# Buck_Regulator_secondary.net
KiCad netlist of a schematic drawn in EAGLE
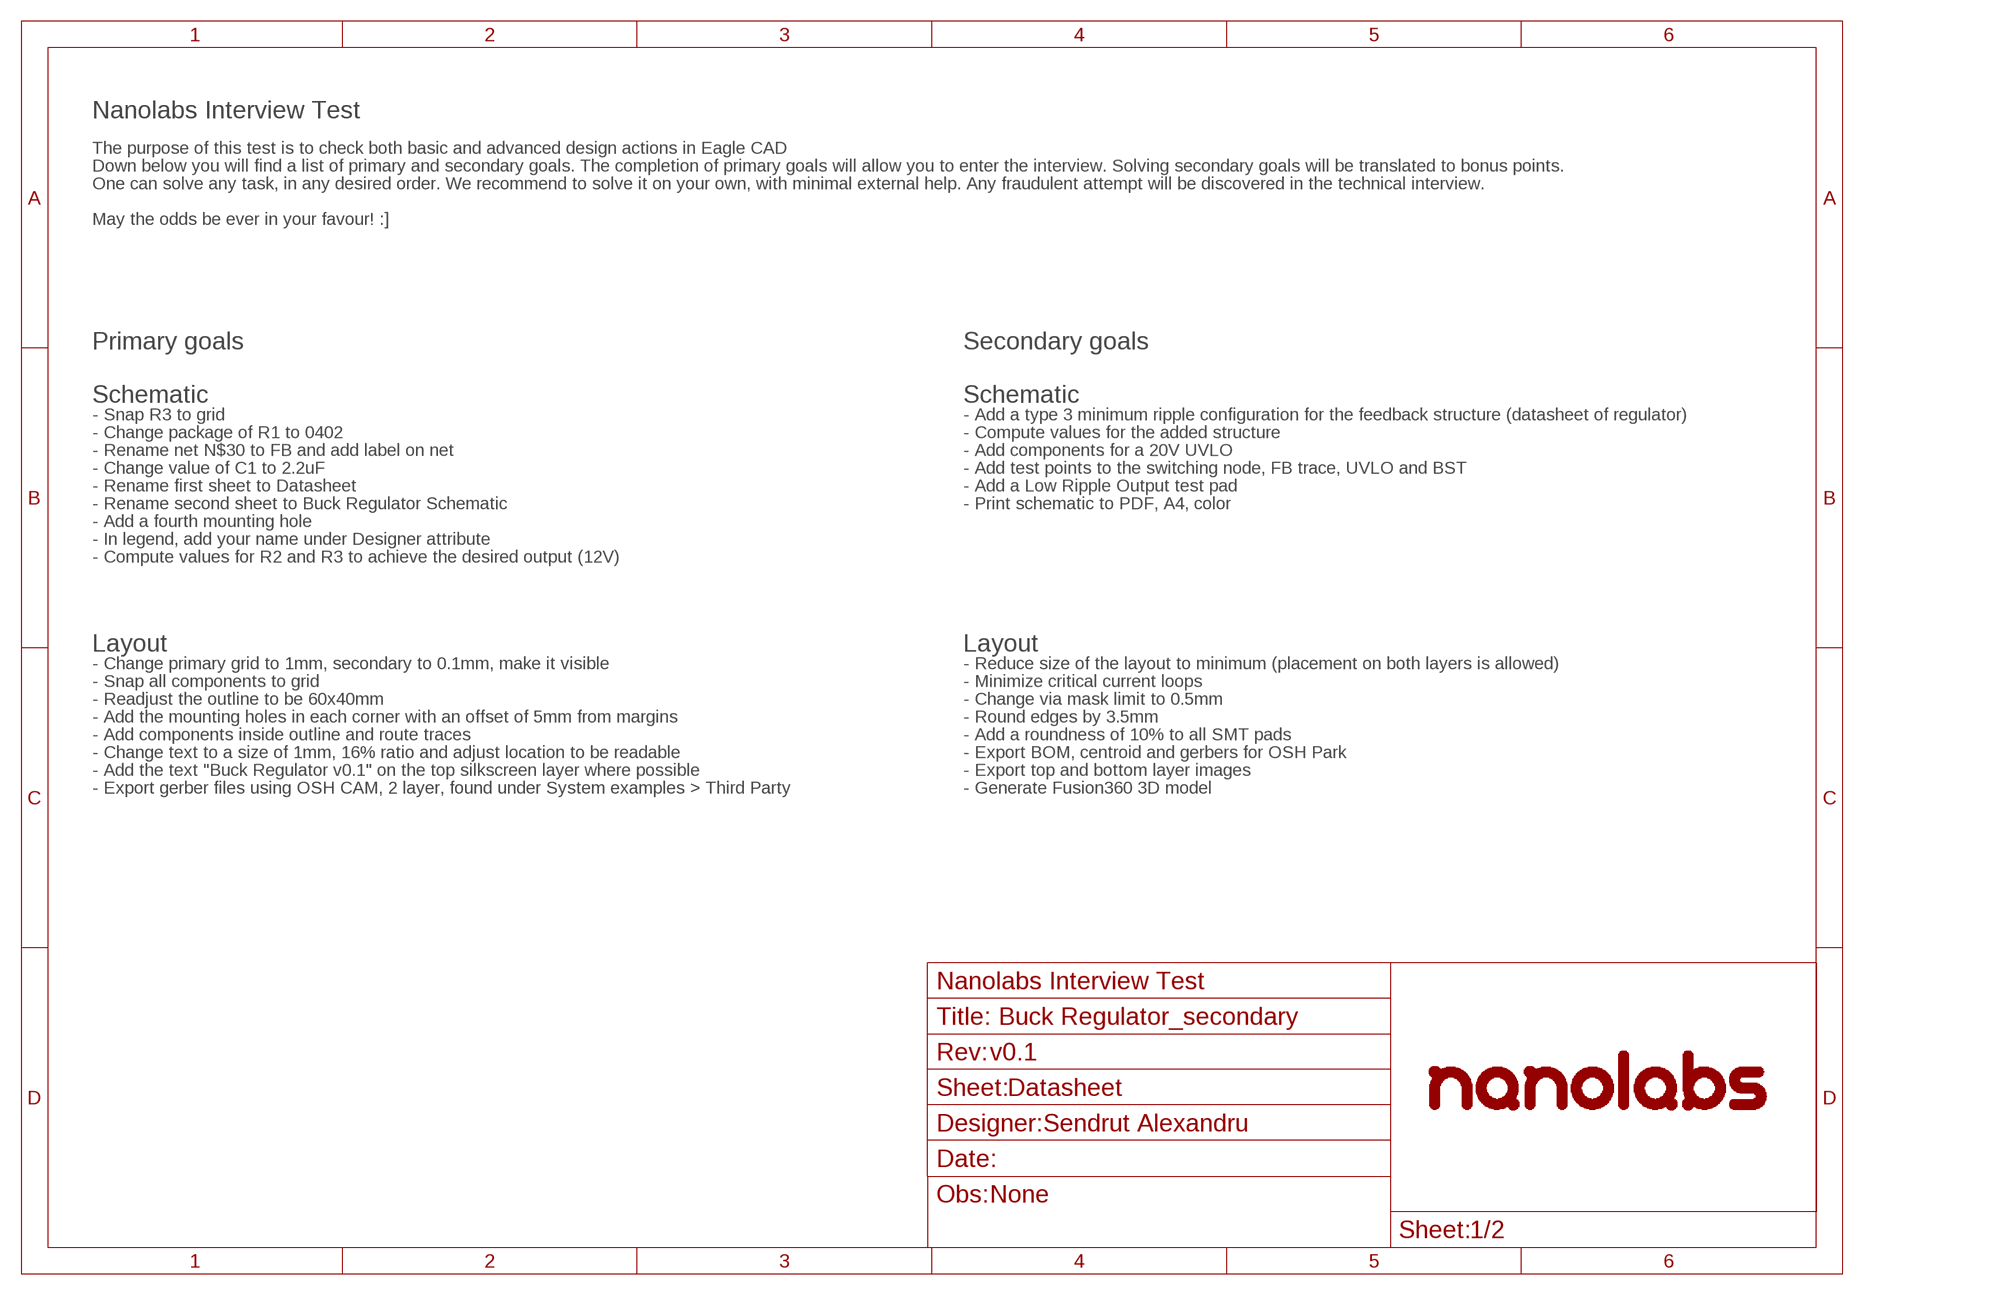
[diagram p0: schematic, sheet 1]
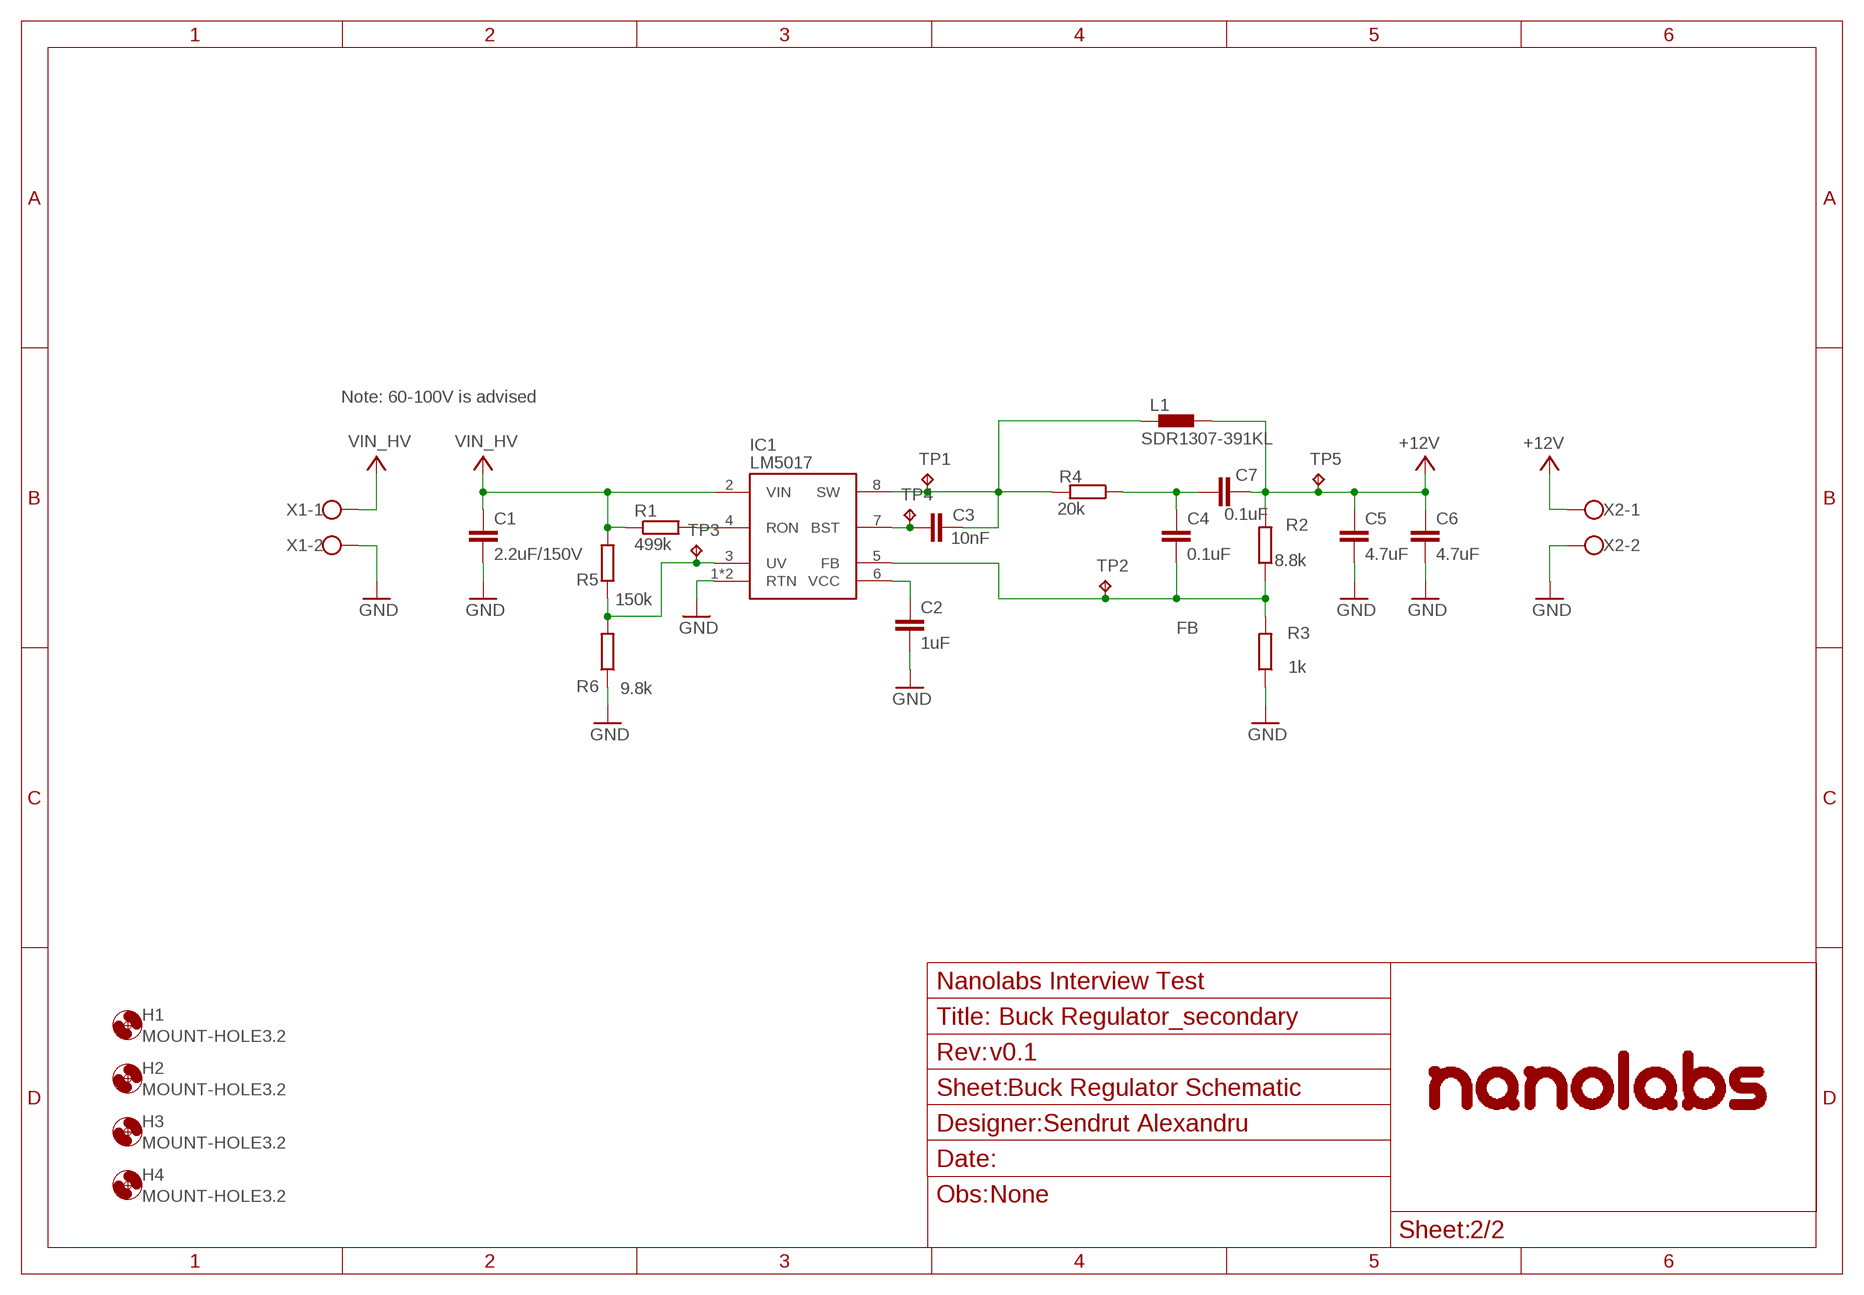
[diagram p1: schematic, sheet 2]

(export (version "E")
  (design (tool "Eeschema 10.0.6"))
  (components
    (comp (ref "C1")
      (value "2.2uF/150V")
      (footprint "eagle-import:C1812")
      (libsource (lib "eagle-import") (part "C-EUC1812"))
    )
    (comp (ref "C2")
      (value "1uF")
      (footprint "eagle-import:C0603")
      (libsource (lib "eagle-import") (part "C-EUC0603"))
    )
    (comp (ref "C3")
      (value "10nF")
      (footprint "eagle-import:C0603")
      (libsource (lib "eagle-import") (part "C-EUC0603"))
    )
    (comp (ref "C4")
      (value "0.1uF")
      (footprint "eagle-import:C0603")
      (libsource (lib "eagle-import") (part "C-EUC0603"))
    )
    (comp (ref "C5")
      (value "4.7uF")
      (footprint "eagle-import:C0603")
      (libsource (lib "eagle-import") (part "C-EUC0603"))
    )
    (comp (ref "C6")
      (value "4.7uF")
      (footprint "eagle-import:C0603")
      (libsource (lib "eagle-import") (part "C-EUC0603"))
    )
    (comp (ref "C7")
      (value "0.1uF")
      (footprint "eagle-import:C0603")
      (libsource (lib "eagle-import") (part "C-EUC0603"))
    )
    (comp (ref "H1")
      (value "MOUNT-HOLE3.2")
      (footprint "eagle-import:3,2")
      (libsource (lib "eagle-import") (part "MOUNT-HOLE3.2"))
    )
    (comp (ref "H2")
      (value "MOUNT-HOLE3.2")
      (footprint "eagle-import:3,2")
      (libsource (lib "eagle-import") (part "MOUNT-HOLE3.2"))
    )
    (comp (ref "H3")
      (value "MOUNT-HOLE3.2")
      (footprint "eagle-import:3,2")
      (libsource (lib "eagle-import") (part "MOUNT-HOLE3.2"))
    )
    (comp (ref "H4")
      (value "MOUNT-HOLE3.2")
      (footprint "eagle-import:3,2")
      (libsource (lib "eagle-import") (part "MOUNT-HOLE3.2"))
    )
    (comp (ref "IC1")
      (value "LM5017")
      (footprint "eagle-import:SO-08-EP")
      (libsource (lib "eagle-import") (part "LM5017"))
    )
    (comp (ref "L1")
      (value "SDR1307-391KL")
      (footprint "eagle-import:SDR1307-391KL")
      (libsource (lib "eagle-import") (part "SDR1307-391KL"))
    )
    (comp (ref "R1")
      (value "499k")
      (footprint "eagle-import:R0402")
      (libsource (lib "eagle-import") (part "R-EU_R0402"))
    )
    (comp (ref "R2")
      (value "8.8k")
      (footprint "eagle-import:R0603")
      (libsource (lib "eagle-import") (part "R-EU_R0603"))
    )
    (comp (ref "R3")
      (value "1k")
      (footprint "eagle-import:R0603")
      (libsource (lib "eagle-import") (part "R-EU_R0603"))
    )
    (comp (ref "R4")
      (value "20k")
      (footprint "eagle-import:R0603")
      (libsource (lib "eagle-import") (part "R-EU_R0603"))
    )
    (comp (ref "R5")
      (value "150k")
      (footprint "eagle-import:R0402")
      (libsource (lib "eagle-import") (part "R-EU_R0402"))
    )
    (comp (ref "R6")
      (value "9.8k")
      (footprint "eagle-import:R0402")
      (libsource (lib "eagle-import") (part "R-EU_R0402"))
    )
    (comp (ref "TP1")
      (value "TPB1,27")
      (footprint "eagle-import:B1,27")
      (libsource (lib "eagle-import") (part "TPB1,27"))
    )
    (comp (ref "TP2")
      (value "TPB1,27")
      (footprint "eagle-import:B1,27")
      (libsource (lib "eagle-import") (part "TPB1,27"))
    )
    (comp (ref "TP3")
      (value "TPB1,27")
      (footprint "eagle-import:B1,27")
      (libsource (lib "eagle-import") (part "TPB1,27"))
    )
    (comp (ref "TP4")
      (value "TPB1,27")
      (footprint "eagle-import:B1,27")
      (libsource (lib "eagle-import") (part "TPB1,27"))
    )
    (comp (ref "TP5")
      (value "TPB1,27")
      (footprint "eagle-import:B1,27")
      (libsource (lib "eagle-import") (part "TPB1,27"))
    )
    (comp (ref "X1")
      (value "W237-102")
      (footprint "eagle-import:W237-102")
      (fields (field (name "MPN") "237-102"))
      (libsource (lib "eagle-import") (part "W237-102"))
    )
    (comp (ref "X2")
      (value "W237-102")
      (footprint "eagle-import:W237-102")
      (fields (field (name "MPN") "237-102"))
      (libsource (lib "eagle-import") (part "W237-102"))
    )
  )
  (nets
    (net (code "1") (name "+12V") (class "Default")
      (node (ref "C5") (pin "1") (pinfunction "1_1") (pintype "passive"))
      (node (ref "C6") (pin "1") (pinfunction "1_1") (pintype "passive"))
      (node (ref "C7") (pin "2") (pinfunction "2_2") (pintype "passive"))
      (node (ref "L1") (pin "2") (pinfunction "2_2") (pintype "passive"))
      (node (ref "R2") (pin "2") (pinfunction "2_2") (pintype "passive"))
      (node (ref "TP5") (pin "TP") (pinfunction "TP_TP") (pintype "input"))
      (node (ref "X2") (pin "1") (pinfunction "KL_1") (pintype "passive"))
    )
    (net (code "2") (name "FB") (class "Default")
      (node (ref "C4") (pin "2") (pinfunction "2_2") (pintype "passive"))
      (node (ref "IC1") (pin "5") (pinfunction "FB_5") (pintype "bidirectional"))
      (node (ref "R2") (pin "1") (pinfunction "1_1") (pintype "passive"))
      (node (ref "R3") (pin "2") (pinfunction "2_2") (pintype "passive"))
      (node (ref "TP2") (pin "TP") (pinfunction "TP_TP") (pintype "input"))
    )
    (net (code "3") (name "GND") (class "Default")
      (node (ref "C1") (pin "2") (pinfunction "2_2") (pintype "passive"))
      (node (ref "C2") (pin "2") (pinfunction "2_2") (pintype "passive"))
      (node (ref "C5") (pin "2") (pinfunction "2_2") (pintype "passive"))
      (node (ref "C6") (pin "2") (pinfunction "2_2") (pintype "passive"))
      (node (ref "IC1") (pin "1") (pinfunction "RTN_1") (pintype "bidirectional"))
      (node (ref "IC1") (pin "9") (pinfunction "RTN_9") (pintype "bidirectional"))
      (node (ref "R3") (pin "1") (pinfunction "1_1") (pintype "passive"))
      (node (ref "R6") (pin "1") (pinfunction "1_1") (pintype "passive"))
      (node (ref "X1") (pin "2") (pinfunction "KL_2") (pintype "passive"))
      (node (ref "X2") (pin "2") (pinfunction "KL_2") (pintype "passive"))
    )
    (net (code "4") (name "Net-(C4-Pad1)") (class "Default")
      (node (ref "C4") (pin "1") (pinfunction "1_1") (pintype "passive"))
      (node (ref "C7") (pin "1") (pinfunction "1_1") (pintype "passive"))
      (node (ref "R4") (pin "1") (pinfunction "1_1") (pintype "passive"))
    )
    (net (code "5") (name "Net-(IC1-BST)") (class "Default")
      (node (ref "C3") (pin "1") (pinfunction "1_1") (pintype "passive"))
      (node (ref "IC1") (pin "7") (pinfunction "BST_7") (pintype "bidirectional"))
      (node (ref "TP4") (pin "TP") (pinfunction "TP_TP") (pintype "input"))
    )
    (net (code "6") (name "Net-(IC1-RON)") (class "Default")
      (node (ref "IC1") (pin "4") (pinfunction "RON_4") (pintype "bidirectional"))
      (node (ref "R1") (pin "2") (pinfunction "2_2") (pintype "passive"))
    )
    (net (code "7") (name "Net-(IC1-SW)") (class "Default")
      (node (ref "C3") (pin "2") (pinfunction "2_2") (pintype "passive"))
      (node (ref "IC1") (pin "8") (pinfunction "SW_8") (pintype "bidirectional"))
      (node (ref "L1") (pin "1") (pinfunction "1_1") (pintype "passive"))
      (node (ref "R4") (pin "2") (pinfunction "2_2") (pintype "passive"))
      (node (ref "TP1") (pin "TP") (pinfunction "TP_TP") (pintype "input"))
    )
    (net (code "8") (name "Net-(IC1-UV)") (class "Default")
      (node (ref "IC1") (pin "3") (pinfunction "UV_3") (pintype "bidirectional"))
      (node (ref "R5") (pin "1") (pinfunction "1_1") (pintype "passive"))
      (node (ref "R6") (pin "2") (pinfunction "2_2") (pintype "passive"))
      (node (ref "TP3") (pin "TP") (pinfunction "TP_TP") (pintype "input"))
    )
    (net (code "9") (name "Net-(IC1-VCC)") (class "Default")
      (node (ref "C2") (pin "1") (pinfunction "1_1") (pintype "passive"))
      (node (ref "IC1") (pin "6") (pinfunction "VCC_6") (pintype "bidirectional"))
    )
    (net (code "10") (name "VIN_HV") (class "Default")
      (node (ref "C1") (pin "1") (pinfunction "1_1") (pintype "passive"))
      (node (ref "IC1") (pin "2") (pinfunction "VIN_2") (pintype "bidirectional"))
      (node (ref "R1") (pin "1") (pinfunction "1_1") (pintype "passive"))
      (node (ref "R5") (pin "2") (pinfunction "2_2") (pintype "passive"))
      (node (ref "X1") (pin "1") (pinfunction "KL_1") (pintype "passive"))
    )
  )
)
